# Teensy_Stromzaehler.net
KiCad netlist of a schematic drawn in EAGLE
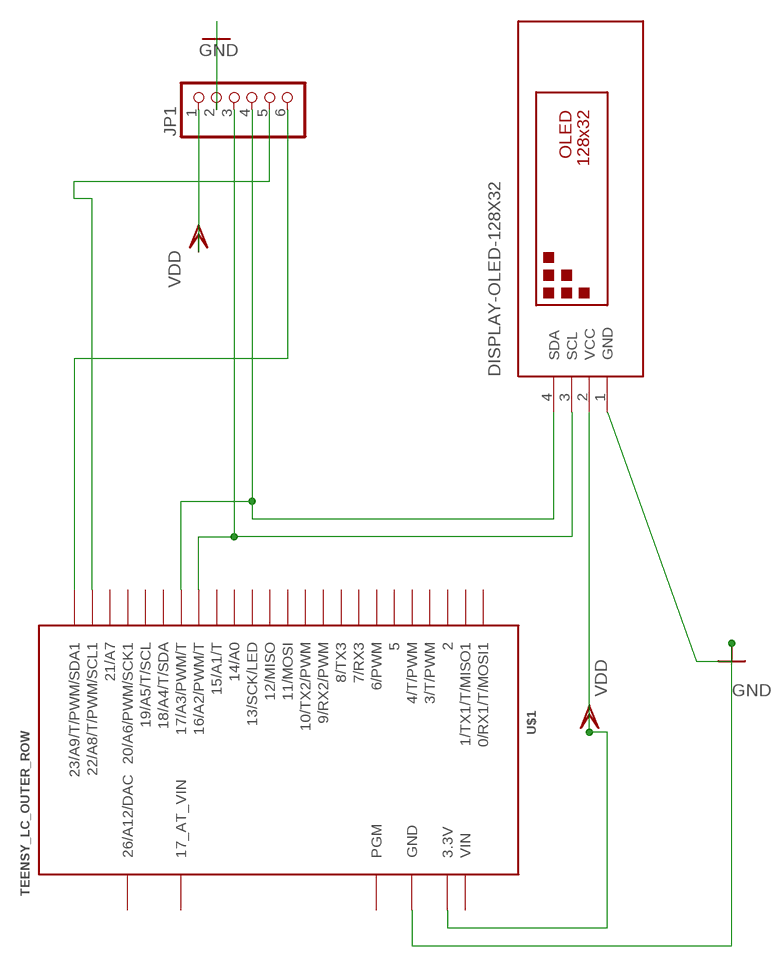
[diagram p0: schematic, sheet 1]

(export (version "E")
  (design (tool "Eeschema 10.0.6"))
  (components
    (comp (ref "JP1")
      (value "PINHD-1X6")
      (footprint "eagle-import:1X06")
      (libsource (lib "eagle-import") (part "PINHD-1X6"))
    )
    (comp (ref "U$1")
      (value "TEENSY_LC_OUTER_ROW")
      (footprint "eagle-import:TEENSY_3.0-3.2&LC_OUTER_ROW")
      (libsource (lib "eagle-import") (part "TEENSY_LC_OUTER_ROW"))
    )
    (comp (ref "U$3")
      (value "DISPLAY-OLED-128X32")
      (footprint "eagle-import:DISPLAY-OLED-128X32")
      (libsource (lib "eagle-import") (part "DISPLAY-OLED-128X32"))
    )
  )
  (nets
    (net (code "1") (name "/26{slash}A12{slash}DAC") (class "Default")
      (node (ref "U$1") (pin "RESET/DAC") (pinfunction "26/A12/DAC_RESET/DAC") (pintype "power_in"))
    )
    (net (code "2") (name "/VIN") (class "Default")
      (node (ref "U$1") (pin "VIN") (pinfunction "VIN_VIN") (pintype "power_in"))
    )
    (net (code "3") (name "GND") (class "Default")
      (node (ref "JP1") (pin "2") (pinfunction "2_2") (pintype "passive"))
      (node (ref "U$1") (pin "AGND") (pinfunction "GND_AGND") (pintype "power_in"))
      (node (ref "U$1") (pin "GND") (pinfunction "GND_GND") (pintype "power_in"))
      (node (ref "U$1") (pin "GND1") (pinfunction "GND_GND1") (pintype "power_in"))
      (node (ref "U$3") (pin "1") (pinfunction "GND_1") (pintype "power_in"))
    )
    (net (code "4") (name "Net-(U$1-16{slash}A2{slash}PWM{slash}T)") (class "Default")
      (node (ref "JP1") (pin "3") (pinfunction "3_3") (pintype "passive"))
      (node (ref "U$1") (pin "16/A2") (pinfunction "16/A2/PWM/T_16/A2") (pintype "bidirectional"))
      (node (ref "U$3") (pin "3") (pinfunction "SCL_3") (pintype "bidirectional"))
    )
    (net (code "5") (name "Net-(U$1-17{slash}A3{slash}PWM{slash}T)") (class "Default")
      (node (ref "JP1") (pin "4") (pinfunction "4_4") (pintype "passive"))
      (node (ref "U$1") (pin "17/A3") (pinfunction "17/A3/PWM/T_17/A3") (pintype "bidirectional"))
      (node (ref "U$3") (pin "4") (pinfunction "SDA_4") (pintype "bidirectional"))
    )
    (net (code "6") (name "Net-(U$1-22{slash}A8{slash}T{slash}PWM{slash}SCL1)") (class "Default")
      (node (ref "JP1") (pin "5") (pinfunction "5_5") (pintype "passive"))
      (node (ref "U$1") (pin "22/A8") (pinfunction "22/A8/T/PWM/SCL1_22/A8") (pintype "bidirectional"))
    )
    (net (code "7") (name "Net-(U$1-23{slash}A9{slash}T{slash}PWM{slash}SDA1)") (class "Default")
      (node (ref "JP1") (pin "6") (pinfunction "6_6") (pintype "passive"))
      (node (ref "U$1") (pin "23/A9") (pinfunction "23/A9/T/PWM/SDA1_23/A9") (pintype "bidirectional"))
    )
    (net (code "8") (name "VDD") (class "Default")
      (node (ref "JP1") (pin "1") (pinfunction "1_1") (pintype "passive"))
      (node (ref "U$1") (pin "3.3V") (pinfunction "3.3V_3.3V") (pintype "power_in"))
      (node (ref "U$1") (pin "3.3V1") (pinfunction "3.3V_3.3V1") (pintype "power_in"))
      (node (ref "U$3") (pin "2") (pinfunction "VCC_2") (pintype "power_in"))
    )
    (net (code "9") (name "unconnected-(U$1-0{slash}RX1{slash}T{slash}MOSI1-Pad0)") (class "Default")
      (node (ref "U$1") (pin "0") (pinfunction "0/RX1/T/MOSI1_0") (pintype "bidirectional"))
    )
    (net (code "10") (name "unconnected-(U$1-1{slash}TX1{slash}T{slash}MISO1-Pad1)") (class "Default")
      (node (ref "U$1") (pin "1") (pinfunction "1/TX1/T/MISO1_1") (pintype "bidirectional"))
    )
    (net (code "11") (name "unconnected-(U$1-3{slash}T{slash}PWM-Pad3)") (class "Default")
      (node (ref "U$1") (pin "3") (pinfunction "3/T/PWM_3") (pintype "bidirectional"))
    )
    (net (code "12") (name "unconnected-(U$1-4{slash}T{slash}PWM-Pad4)") (class "Default")
      (node (ref "U$1") (pin "4") (pinfunction "4/T/PWM_4") (pintype "bidirectional"))
    )
    (net (code "13") (name "unconnected-(U$1-6{slash}PWM-Pad6)") (class "Default")
      (node (ref "U$1") (pin "6") (pinfunction "6/PWM_6") (pintype "bidirectional"))
    )
    (net (code "14") (name "unconnected-(U$1-7{slash}RX3-Pad7)") (class "Default")
      (node (ref "U$1") (pin "7") (pinfunction "7/RX3_7") (pintype "bidirectional"))
    )
    (net (code "15") (name "unconnected-(U$1-8{slash}TX3-Pad8)") (class "Default")
      (node (ref "U$1") (pin "8") (pinfunction "8/TX3_8") (pintype "bidirectional"))
    )
    (net (code "16") (name "unconnected-(U$1-9{slash}RX2{slash}PWM-Pad9)") (class "Default")
      (node (ref "U$1") (pin "9") (pinfunction "9/RX2/PWM_9") (pintype "bidirectional"))
    )
    (net (code "17") (name "unconnected-(U$1-10{slash}TX2{slash}PWM-Pad10)") (class "Default")
      (node (ref "U$1") (pin "10") (pinfunction "10/TX2/PWM_10") (pintype "bidirectional"))
    )
    (net (code "18") (name "unconnected-(U$1-11{slash}MOSI-Pad11)") (class "Default")
      (node (ref "U$1") (pin "11") (pinfunction "11/MOSI_11") (pintype "bidirectional"))
    )
    (net (code "19") (name "unconnected-(U$1-12{slash}MISO-Pad12)") (class "Default")
      (node (ref "U$1") (pin "12") (pinfunction "12/MISO_12") (pintype "bidirectional"))
    )
    (net (code "20") (name "unconnected-(U$1-13{slash}SCK{slash}LED-Pad13)") (class "Default")
      (node (ref "U$1") (pin "13") (pinfunction "13/SCK/LED_13") (pintype "bidirectional"))
    )
    (net (code "21") (name "unconnected-(U$1-15{slash}A1{slash}T-Pad15{slash}A1)") (class "Default")
      (node (ref "U$1") (pin "15/A1") (pinfunction "15/A1/T_15/A1") (pintype "bidirectional"))
    )
    (net (code "22") (name "unconnected-(U$1-17_AT_VIN-PadVBAT)") (class "Default")
      (node (ref "U$1") (pin "VBAT") (pinfunction "17_AT_VIN_VBAT") (pintype "bidirectional"))
    )
    (net (code "23") (name "unconnected-(U$1-18{slash}A4{slash}T{slash}SDA-Pad18{slash}A4)") (class "Default")
      (node (ref "U$1") (pin "18/A4") (pinfunction "18/A4/T/SDA_18/A4") (pintype "bidirectional"))
    )
    (net (code "24") (name "unconnected-(U$1-19{slash}A5{slash}T{slash}SCL-Pad19{slash}A5)") (class "Default")
      (node (ref "U$1") (pin "19/A5") (pinfunction "19/A5/T/SCL_19/A5") (pintype "bidirectional"))
    )
    (net (code "25") (name "unconnected-(U$1-20{slash}A6{slash}PWM{slash}SCK1-Pad20{slash}A6)") (class "Default")
      (node (ref "U$1") (pin "20/A6") (pinfunction "20/A6/PWM/SCK1_20/A6") (pintype "bidirectional"))
    )
    (net (code "26") (name "unconnected-(U$1-Pad2)") (class "Default")
      (node (ref "U$1") (pin "2") (pinfunction "2_2") (pintype "bidirectional"))
    )
    (net (code "27") (name "unconnected-(U$1-Pad5)") (class "Default")
      (node (ref "U$1") (pin "5") (pinfunction "5_5") (pintype "bidirectional"))
    )
    (net (code "28") (name "unconnected-(U$1-Pad14{slash}A0)") (class "Default")
      (node (ref "U$1") (pin "14/A0") (pinfunction "14/A0_14/A0") (pintype "bidirectional"))
    )
    (net (code "29") (name "unconnected-(U$1-Pad21{slash}A7)") (class "Default")
      (node (ref "U$1") (pin "21/A7") (pinfunction "21/A7_21/A7") (pintype "bidirectional"))
    )
    (net (code "30") (name "unconnected-(U$1-PadPGM)") (class "Default")
      (node (ref "U$1") (pin "PGM") (pinfunction "PGM_PGM") (pintype "bidirectional"))
    )
  )
)
